# pwmIC.net
KiCad netlist of a schematic drawn in Altium Designer
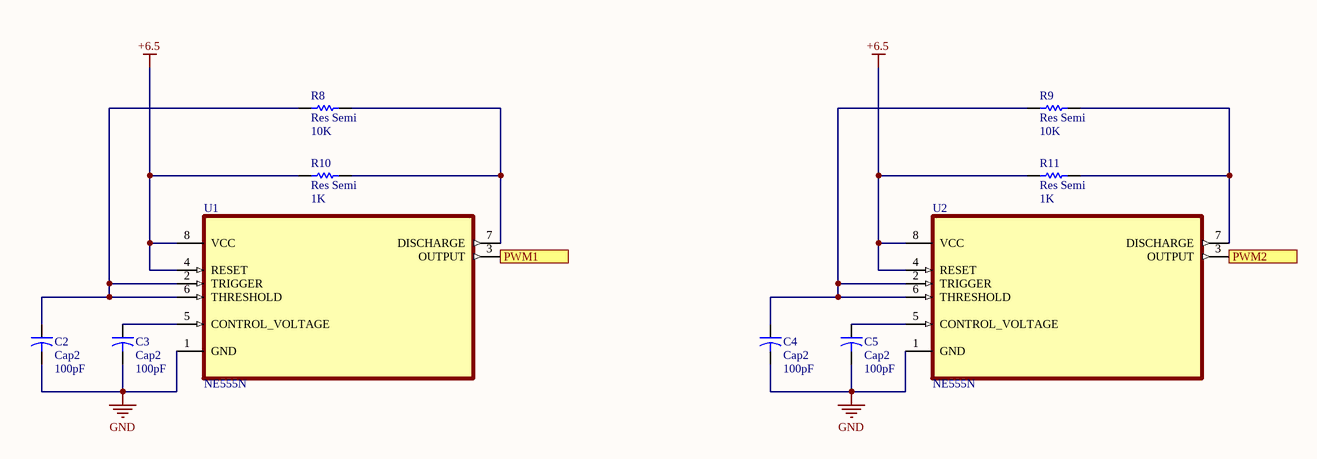
[diagram p0: pwmIC.SchDoc]

(export (version "E")
  (design (tool "Eeschema 10.0.6"))
  (components
    (comp (ref "C2")
      (value "Cap2")
      (footprint "CAPR5-4X5")
      (description "Capacitor")
      (fields (field (name "ALTIUM_VALUE") "100pF") (field (name "PUBLISHER") "Altium Limited"))
      (libsource (lib "Miscellaneous Devices") (part "Cap2"))
    )
    (comp (ref "C3")
      (value "Cap2")
      (footprint "CAPR5-4X5")
      (description "Capacitor")
      (fields (field (name "ALTIUM_VALUE") "100pF") (field (name "PUBLISHER") "Altium Limited"))
      (libsource (lib "Miscellaneous Devices") (part "Cap2"))
    )
    (comp (ref "C4")
      (value "Cap2")
      (footprint "CAPR5-4X5")
      (description "Capacitor")
      (fields (field (name "ALTIUM_VALUE") "100pF") (field (name "PUBLISHER") "Altium Limited"))
      (libsource (lib "Miscellaneous Devices") (part "Cap2"))
    )
    (comp (ref "C5")
      (value "Cap2")
      (footprint "CAPR5-4X5")
      (description "Capacitor")
      (fields (field (name "ALTIUM_VALUE") "100pF") (field (name "PUBLISHER") "Altium Limited"))
      (libsource (lib "Miscellaneous Devices") (part "Cap2"))
    )
    (comp (ref "R8")
      (value "Res Semi")
      (footprint "AXIAL-0.5")
      (description "Semiconductor Resistor")
      (fields (field (name "ALTIUM_VALUE") "10K") (field (name "PUBLISHER") "Altium Limited"))
      (libsource (lib "Miscellaneous Devices") (part "Res Semi"))
    )
    (comp (ref "R9")
      (value "Res Semi")
      (footprint "AXIAL-0.5")
      (description "Semiconductor Resistor")
      (fields (field (name "ALTIUM_VALUE") "10K") (field (name "PUBLISHER") "Altium Limited"))
      (libsource (lib "Miscellaneous Devices") (part "Res Semi"))
    )
    (comp (ref "R10")
      (value "Res Semi")
      (footprint "AXIAL-0.5")
      (description "Semiconductor Resistor")
      (fields (field (name "ALTIUM_VALUE") "1K") (field (name "PUBLISHER") "Altium Limited"))
      (libsource (lib "Miscellaneous Devices") (part "Res Semi"))
    )
    (comp (ref "R11")
      (value "Res Semi")
      (footprint "AXIAL-0.5")
      (description "Semiconductor Resistor")
      (fields (field (name "ALTIUM_VALUE") "1K") (field (name "PUBLISHER") "Altium Limited"))
      (libsource (lib "Miscellaneous Devices") (part "Res Semi"))
    )
    (comp (ref "U1")
      (value "NE555N")
      (footprint "NE555 -T")
      (description "555 Type, Timer/Oscillator _Single_ IC 8-DIP")
      (fields (field (name "MF") "ON Semiconductor"))
      (libsource (lib "RoketAnaSistemSematikKütüphane") (part "NE555N"))
    )
    (comp (ref "U2")
      (value "NE555N")
      (footprint "NE555 -T")
      (description "555 Type, Timer/Oscillator _Single_ IC 8-DIP")
      (fields (field (name "MF") "ON Semiconductor"))
      (libsource (lib "RoketAnaSistemSematikKütüphane") (part "NE555N"))
    )
  )
  (nets
    (net (code "1") (name "+6.5") (class "Default")
      (node (ref "R10") (pin "1") (pinfunction "1_1") (pintype "passive"))
      (node (ref "R11") (pin "1") (pinfunction "1_1") (pintype "passive"))
      (node (ref "U1") (pin "4") (pinfunction "RESET_4") (pintype "input"))
      (node (ref "U1") (pin "8") (pinfunction "VCC_8") (pintype "power_in"))
      (node (ref "U2") (pin "4") (pinfunction "RESET_4") (pintype "input"))
      (node (ref "U2") (pin "8") (pinfunction "VCC_8") (pintype "power_in"))
    )
    (net (code "2") (name "/PWM1") (class "Default")
      (node (ref "U1") (pin "3") (pinfunction "OUTPUT_3") (pintype "output"))
    )
    (net (code "3") (name "/PWM2") (class "Default")
      (node (ref "U2") (pin "3") (pinfunction "OUTPUT_3") (pintype "output"))
    )
    (net (code "4") (name "GND") (class "Default")
      (node (ref "C2") (pin "2") (pinfunction "2_2") (pintype "passive"))
      (node (ref "C3") (pin "2") (pinfunction "2_2") (pintype "passive"))
      (node (ref "C4") (pin "2") (pinfunction "2_2") (pintype "passive"))
      (node (ref "C5") (pin "2") (pinfunction "2_2") (pintype "passive"))
      (node (ref "U1") (pin "1") (pinfunction "GND_1") (pintype "passive"))
      (node (ref "U2") (pin "1") (pinfunction "GND_1") (pintype "passive"))
    )
    (net (code "5") (name "Net-(U1-CONTROL_VOLTAGE)") (class "Default")
      (node (ref "C3") (pin "1") (pinfunction "1_1") (pintype "passive"))
      (node (ref "U1") (pin "5") (pinfunction "CONTROL_VOLTAGE_5") (pintype "input"))
    )
    (net (code "6") (name "Net-(U1-DISCHARGE)") (class "Default")
      (node (ref "R10") (pin "2") (pinfunction "2_2") (pintype "passive"))
      (node (ref "R8") (pin "2") (pinfunction "2_2") (pintype "passive"))
      (node (ref "U1") (pin "7") (pinfunction "DISCHARGE_7") (pintype "output"))
    )
    (net (code "7") (name "Net-(U1-THRESHOLD)") (class "Default")
      (node (ref "C2") (pin "1") (pinfunction "1_1") (pintype "passive"))
      (node (ref "R8") (pin "1") (pinfunction "1_1") (pintype "passive"))
      (node (ref "U1") (pin "2") (pinfunction "TRIGGER_2") (pintype "input"))
      (node (ref "U1") (pin "6") (pinfunction "THRESHOLD_6") (pintype "input"))
    )
    (net (code "8") (name "Net-(U2-CONTROL_VOLTAGE)") (class "Default")
      (node (ref "C5") (pin "1") (pinfunction "1_1") (pintype "passive"))
      (node (ref "U2") (pin "5") (pinfunction "CONTROL_VOLTAGE_5") (pintype "input"))
    )
    (net (code "9") (name "Net-(U2-DISCHARGE)") (class "Default")
      (node (ref "R11") (pin "2") (pinfunction "2_2") (pintype "passive"))
      (node (ref "R9") (pin "2") (pinfunction "2_2") (pintype "passive"))
      (node (ref "U2") (pin "7") (pinfunction "DISCHARGE_7") (pintype "output"))
    )
    (net (code "10") (name "Net-(U2-THRESHOLD)") (class "Default")
      (node (ref "C4") (pin "1") (pinfunction "1_1") (pintype "passive"))
      (node (ref "R9") (pin "1") (pinfunction "1_1") (pintype "passive"))
      (node (ref "U2") (pin "2") (pinfunction "TRIGGER_2") (pintype "input"))
      (node (ref "U2") (pin "6") (pinfunction "THRESHOLD_6") (pintype "input"))
    )
  )
)
